# Joypad.net
KiCad netlist of a schematic drawn in EAGLE
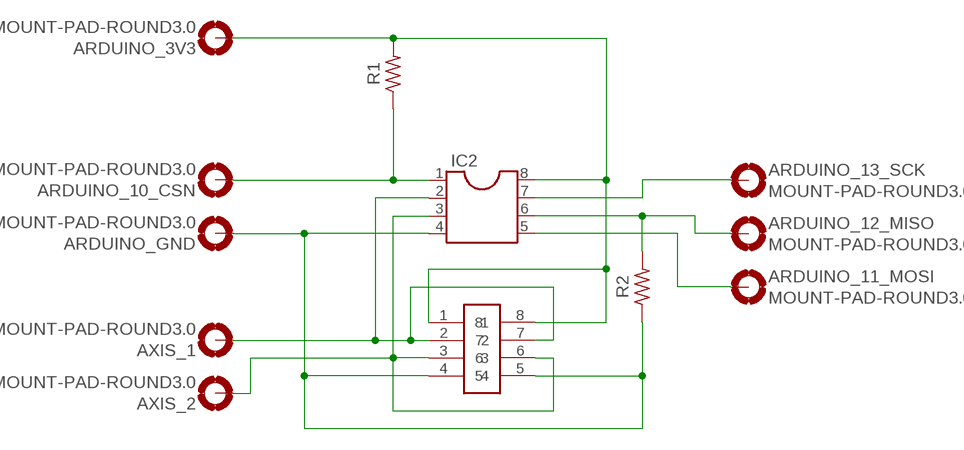
[diagram p0: schematic, sheet 1]

(export (version "E")
  (design (tool "Eeschema 10.0.6"))
  (components
    (comp (ref "ARDUINO_3V3")
      (value "MOUNT-PAD-ROUND3.0")
      (footprint "eagle-import:3,0-PAD")
      (libsource (lib "eagle-import") (part "MOUNT-PAD-ROUND3.0"))
    )
    (comp (ref "ARDUINO_10_CSN")
      (value "MOUNT-PAD-ROUND3.0")
      (footprint "eagle-import:3,0-PAD")
      (libsource (lib "eagle-import") (part "MOUNT-PAD-ROUND3.0"))
    )
    (comp (ref "ARDUINO_11_MOSI")
      (value "MOUNT-PAD-ROUND3.0")
      (footprint "eagle-import:3,0-PAD")
      (libsource (lib "eagle-import") (part "MOUNT-PAD-ROUND3.0"))
    )
    (comp (ref "ARDUINO_12_MISO")
      (value "MOUNT-PAD-ROUND3.0")
      (footprint "eagle-import:3,0-PAD")
      (libsource (lib "eagle-import") (part "MOUNT-PAD-ROUND3.0"))
    )
    (comp (ref "ARDUINO_13_SCK")
      (value "MOUNT-PAD-ROUND3.0")
      (footprint "eagle-import:3,0-PAD")
      (libsource (lib "eagle-import") (part "MOUNT-PAD-ROUND3.0"))
    )
    (comp (ref "ARDUINO_GND")
      (value "MOUNT-PAD-ROUND3.0")
      (footprint "eagle-import:3,0-PAD")
      (libsource (lib "eagle-import") (part "MOUNT-PAD-ROUND3.0"))
    )
    (comp (ref "AXIS_1")
      (value "MOUNT-PAD-ROUND3.0")
      (footprint "eagle-import:3,0-PAD")
      (libsource (lib "eagle-import") (part "MOUNT-PAD-ROUND3.0"))
    )
    (comp (ref "AXIS_2")
      (value "MOUNT-PAD-ROUND3.0")
      (footprint "eagle-import:3,0-PAD")
      (libsource (lib "eagle-import") (part "MOUNT-PAD-ROUND3.0"))
    )
    (comp (ref "IC2")
      (value "DIL8S")
      (footprint "eagle-import:SOCKET-08")
      (libsource (lib "eagle-import") (part "DIL8S"))
    )
    (comp (ref "R1")
      (value "R-US_AXIAL-7.2MM-PITCH")
      (footprint "eagle-import:RESAD724W46L381D178B")
      (libsource (lib "eagle-import") (part "R-USAXIAL-7.2MM-PITCH_"))
    )
    (comp (ref "R2")
      (value "R-US_AXIAL-7.2MM-PITCH")
      (footprint "eagle-import:RESAD724W46L381D178B")
      (libsource (lib "eagle-import") (part "R-USAXIAL-7.2MM-PITCH_"))
    )
    (comp (ref "U$1")
      (value "JOYSTICK")
      (footprint "eagle-import:JOYSTICK")
      (libsource (lib "eagle-import") (part "JOYSTICK"))
    )
  )
  (nets
    (net (code "1") (name "Net-(ARDUINO_3V3-MOUNT)") (class "Default")
      (node (ref "ARDUINO_3V3") (pin "B3,0") (pinfunction "MOUNT_B3,0") (pintype "passive"))
      (node (ref "IC2") (pin "8") (pinfunction "8_8") (pintype "passive"))
      (node (ref "R1") (pin "2") (pinfunction "2_2") (pintype "passive"))
      (node (ref "U$1") (pin "1") (pinfunction "1_1") (pintype "bidirectional"))
      (node (ref "U$1") (pin "8") (pinfunction "8_8") (pintype "bidirectional"))
    )
    (net (code "2") (name "Net-(ARDUINO_10_CSN-MOUNT)") (class "Default")
      (node (ref "ARDUINO_10_CSN") (pin "B3,0") (pinfunction "MOUNT_B3,0") (pintype "passive"))
      (node (ref "IC2") (pin "1") (pinfunction "1_1") (pintype "passive"))
      (node (ref "R1") (pin "1") (pinfunction "1_1") (pintype "passive"))
    )
    (net (code "3") (name "Net-(ARDUINO_11_MOSI-MOUNT)") (class "Default")
      (node (ref "ARDUINO_11_MOSI") (pin "B3,0") (pinfunction "MOUNT_B3,0") (pintype "passive"))
      (node (ref "IC2") (pin "5") (pinfunction "5_5") (pintype "passive"))
    )
    (net (code "4") (name "Net-(ARDUINO_12_MISO-MOUNT)") (class "Default")
      (node (ref "ARDUINO_12_MISO") (pin "B3,0") (pinfunction "MOUNT_B3,0") (pintype "passive"))
      (node (ref "IC2") (pin "6") (pinfunction "6_6") (pintype "passive"))
      (node (ref "R2") (pin "2") (pinfunction "2_2") (pintype "passive"))
    )
    (net (code "5") (name "Net-(ARDUINO_13_SCK-MOUNT)") (class "Default")
      (node (ref "ARDUINO_13_SCK") (pin "B3,0") (pinfunction "MOUNT_B3,0") (pintype "passive"))
      (node (ref "IC2") (pin "7") (pinfunction "7_7") (pintype "passive"))
    )
    (net (code "6") (name "Net-(ARDUINO_GND-MOUNT)") (class "Default")
      (node (ref "ARDUINO_GND") (pin "B3,0") (pinfunction "MOUNT_B3,0") (pintype "passive"))
      (node (ref "IC2") (pin "4") (pinfunction "4_4") (pintype "passive"))
      (node (ref "R2") (pin "1") (pinfunction "1_1") (pintype "passive"))
      (node (ref "U$1") (pin "4") (pinfunction "4_4") (pintype "bidirectional"))
      (node (ref "U$1") (pin "5") (pinfunction "5_5") (pintype "bidirectional"))
    )
    (net (code "7") (name "Net-(AXIS_1-MOUNT)") (class "Default")
      (node (ref "AXIS_1") (pin "B3,0") (pinfunction "MOUNT_B3,0") (pintype "passive"))
      (node (ref "IC2") (pin "2") (pinfunction "2_2") (pintype "passive"))
      (node (ref "U$1") (pin "2") (pinfunction "2_2") (pintype "bidirectional"))
      (node (ref "U$1") (pin "7") (pinfunction "7_7") (pintype "bidirectional"))
    )
    (net (code "8") (name "Net-(AXIS_2-MOUNT)") (class "Default")
      (node (ref "AXIS_2") (pin "B3,0") (pinfunction "MOUNT_B3,0") (pintype "passive"))
      (node (ref "IC2") (pin "3") (pinfunction "3_3") (pintype "passive"))
      (node (ref "U$1") (pin "3") (pinfunction "3_3") (pintype "bidirectional"))
      (node (ref "U$1") (pin "6") (pinfunction "6_6") (pintype "bidirectional"))
    )
  )
)
